# WATCHDOG.net
KiCad netlist of a schematic drawn in Altium Designer
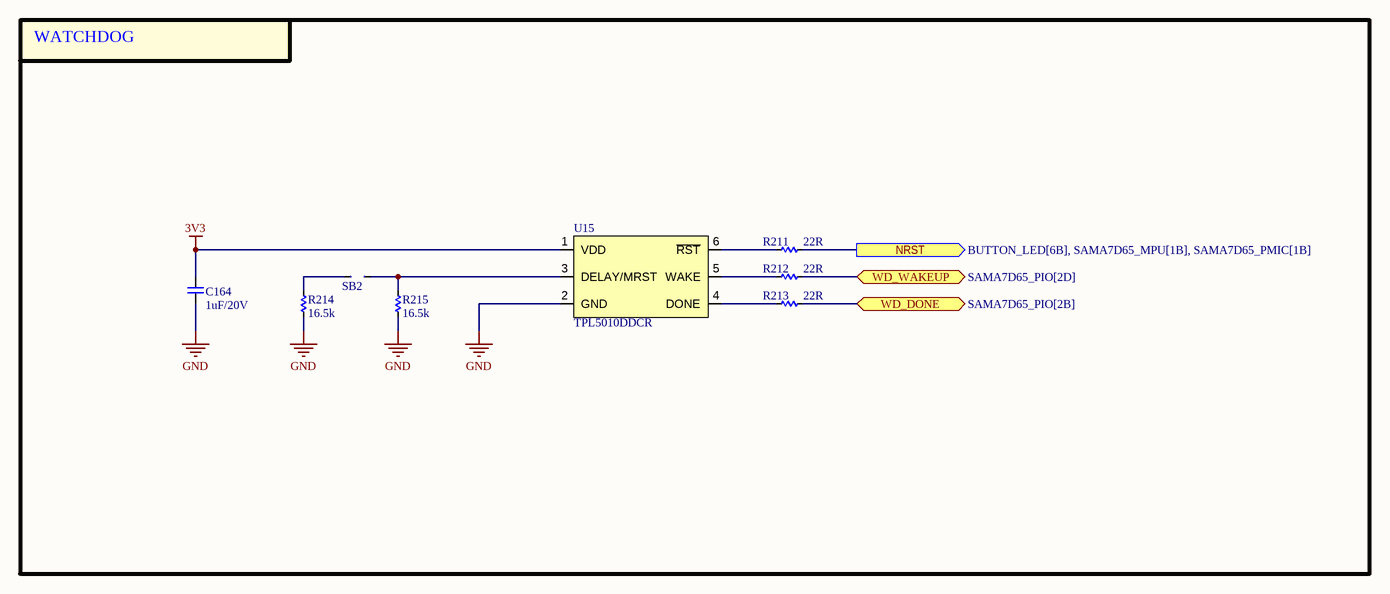
[diagram p0: WATCHDOG.SchDoc]

(export (version "E")
  (design (tool "Eeschema 10.0.6"))
  (components
    (comp (ref "C164")
      (value "1uF/20V")
      (footprint "CAP_C_1005X50_L")
      (description "CAP CHIP")
      (libsource (lib "IFBschelib") (part "_CAP_C_2"))
    )
    (comp (ref "R211")
      (value "22R")
      (footprint "RES_C_1005x30_L")
      (description "RES")
      (libsource (lib "IFBschelib") (part "_RES_B_2"))
    )
    (comp (ref "R212")
      (value "22R")
      (footprint "RES_C_1005x30_L")
      (description "RES")
      (libsource (lib "IFBschelib") (part "_RES_B_2"))
    )
    (comp (ref "R213")
      (value "22R")
      (footprint "RES_C_1005x30_L")
      (description "RES")
      (libsource (lib "IFBschelib") (part "_RES_B_2"))
    )
    (comp (ref "R214")
      (value "16.5k")
      (footprint "RES_C_1005x30_L")
      (description "RES")
      (libsource (lib "IFBschelib") (part "_RES_B_2"))
    )
    (comp (ref "R215")
      (value "16.5k")
      (footprint "RES_C_1005x30_L")
      (description "RES")
      (libsource (lib "IFBschelib") (part "_RES_B_2"))
    )
    (comp (ref "SB2")
      (value "JUMPER")
      (footprint "JUMPER_1608")
      (libsource (lib "IFBschelib") (part "JUMPER"))
    )
    (comp (ref "U15")
      (value "TPL5010DDCR")
      (footprint "TPL5010DDCR")
      (description "OSC PROG TIMER TSOT23-6")
      (libsource (lib "IFBschelib") (part "TPL5010DDCR"))
    )
  )
  (nets
    (net (code "1") (name "/NRST") (class "Default")
      (node (ref "R211") (pin "2") (pinfunction "2_2") (pintype "passive"))
    )
    (net (code "2") (name "/WD_DONE") (class "Default")
      (node (ref "R213") (pin "2") (pinfunction "2_2") (pintype "passive"))
    )
    (net (code "3") (name "/WD_WAKEUP") (class "Default")
      (node (ref "R212") (pin "2") (pinfunction "2_2") (pintype "passive"))
    )
    (net (code "4") (name "3V3") (class "Default")
      (node (ref "C164") (pin "2") (pinfunction "2_2") (pintype "passive"))
      (node (ref "U15") (pin "1") (pinfunction "VDD_1") (pintype "passive"))
    )
    (net (code "5") (name "GND") (class "Default")
      (node (ref "C164") (pin "1") (pinfunction "1_1") (pintype "passive"))
      (node (ref "R214") (pin "2") (pinfunction "2_2") (pintype "passive"))
      (node (ref "R215") (pin "2") (pinfunction "2_2") (pintype "passive"))
      (node (ref "U15") (pin "2") (pinfunction "GND_2") (pintype "passive"))
    )
    (net (code "6") (name "Net-(R214-Pad1)") (class "Default")
      (node (ref "R214") (pin "1") (pinfunction "1_1") (pintype "passive"))
      (node (ref "SB2") (pin "1") (pinfunction "1_1") (pintype "passive"))
    )
    (net (code "7") (name "Net-(U15-DELAY{slash}MRST)") (class "Default")
      (node (ref "R215") (pin "1") (pinfunction "1_1") (pintype "passive"))
      (node (ref "SB2") (pin "2") (pinfunction "2_2") (pintype "passive"))
      (node (ref "U15") (pin "3") (pinfunction "DELAY/MRST_3") (pintype "passive"))
    )
    (net (code "8") (name "Net-(U15-DONE)") (class "Default")
      (node (ref "R213") (pin "1") (pinfunction "1_1") (pintype "passive"))
      (node (ref "U15") (pin "4") (pinfunction "DONE_4") (pintype "passive"))
    )
    (net (code "9") (name "Net-(U15-WAKE)") (class "Default")
      (node (ref "R212") (pin "1") (pinfunction "1_1") (pintype "passive"))
      (node (ref "U15") (pin "5") (pinfunction "WAKE_5") (pintype "passive"))
    )
    (net (code "10") (name "Net-(U15-~{RST})") (class "Default")
      (node (ref "R211") (pin "1") (pinfunction "1_1") (pintype "passive"))
      (node (ref "U15") (pin "6") (pinfunction "~{RST}_6") (pintype "passive"))
    )
  )
)
